# schematic.net
KiCad netlist of a schematic drawn in EasyEDA
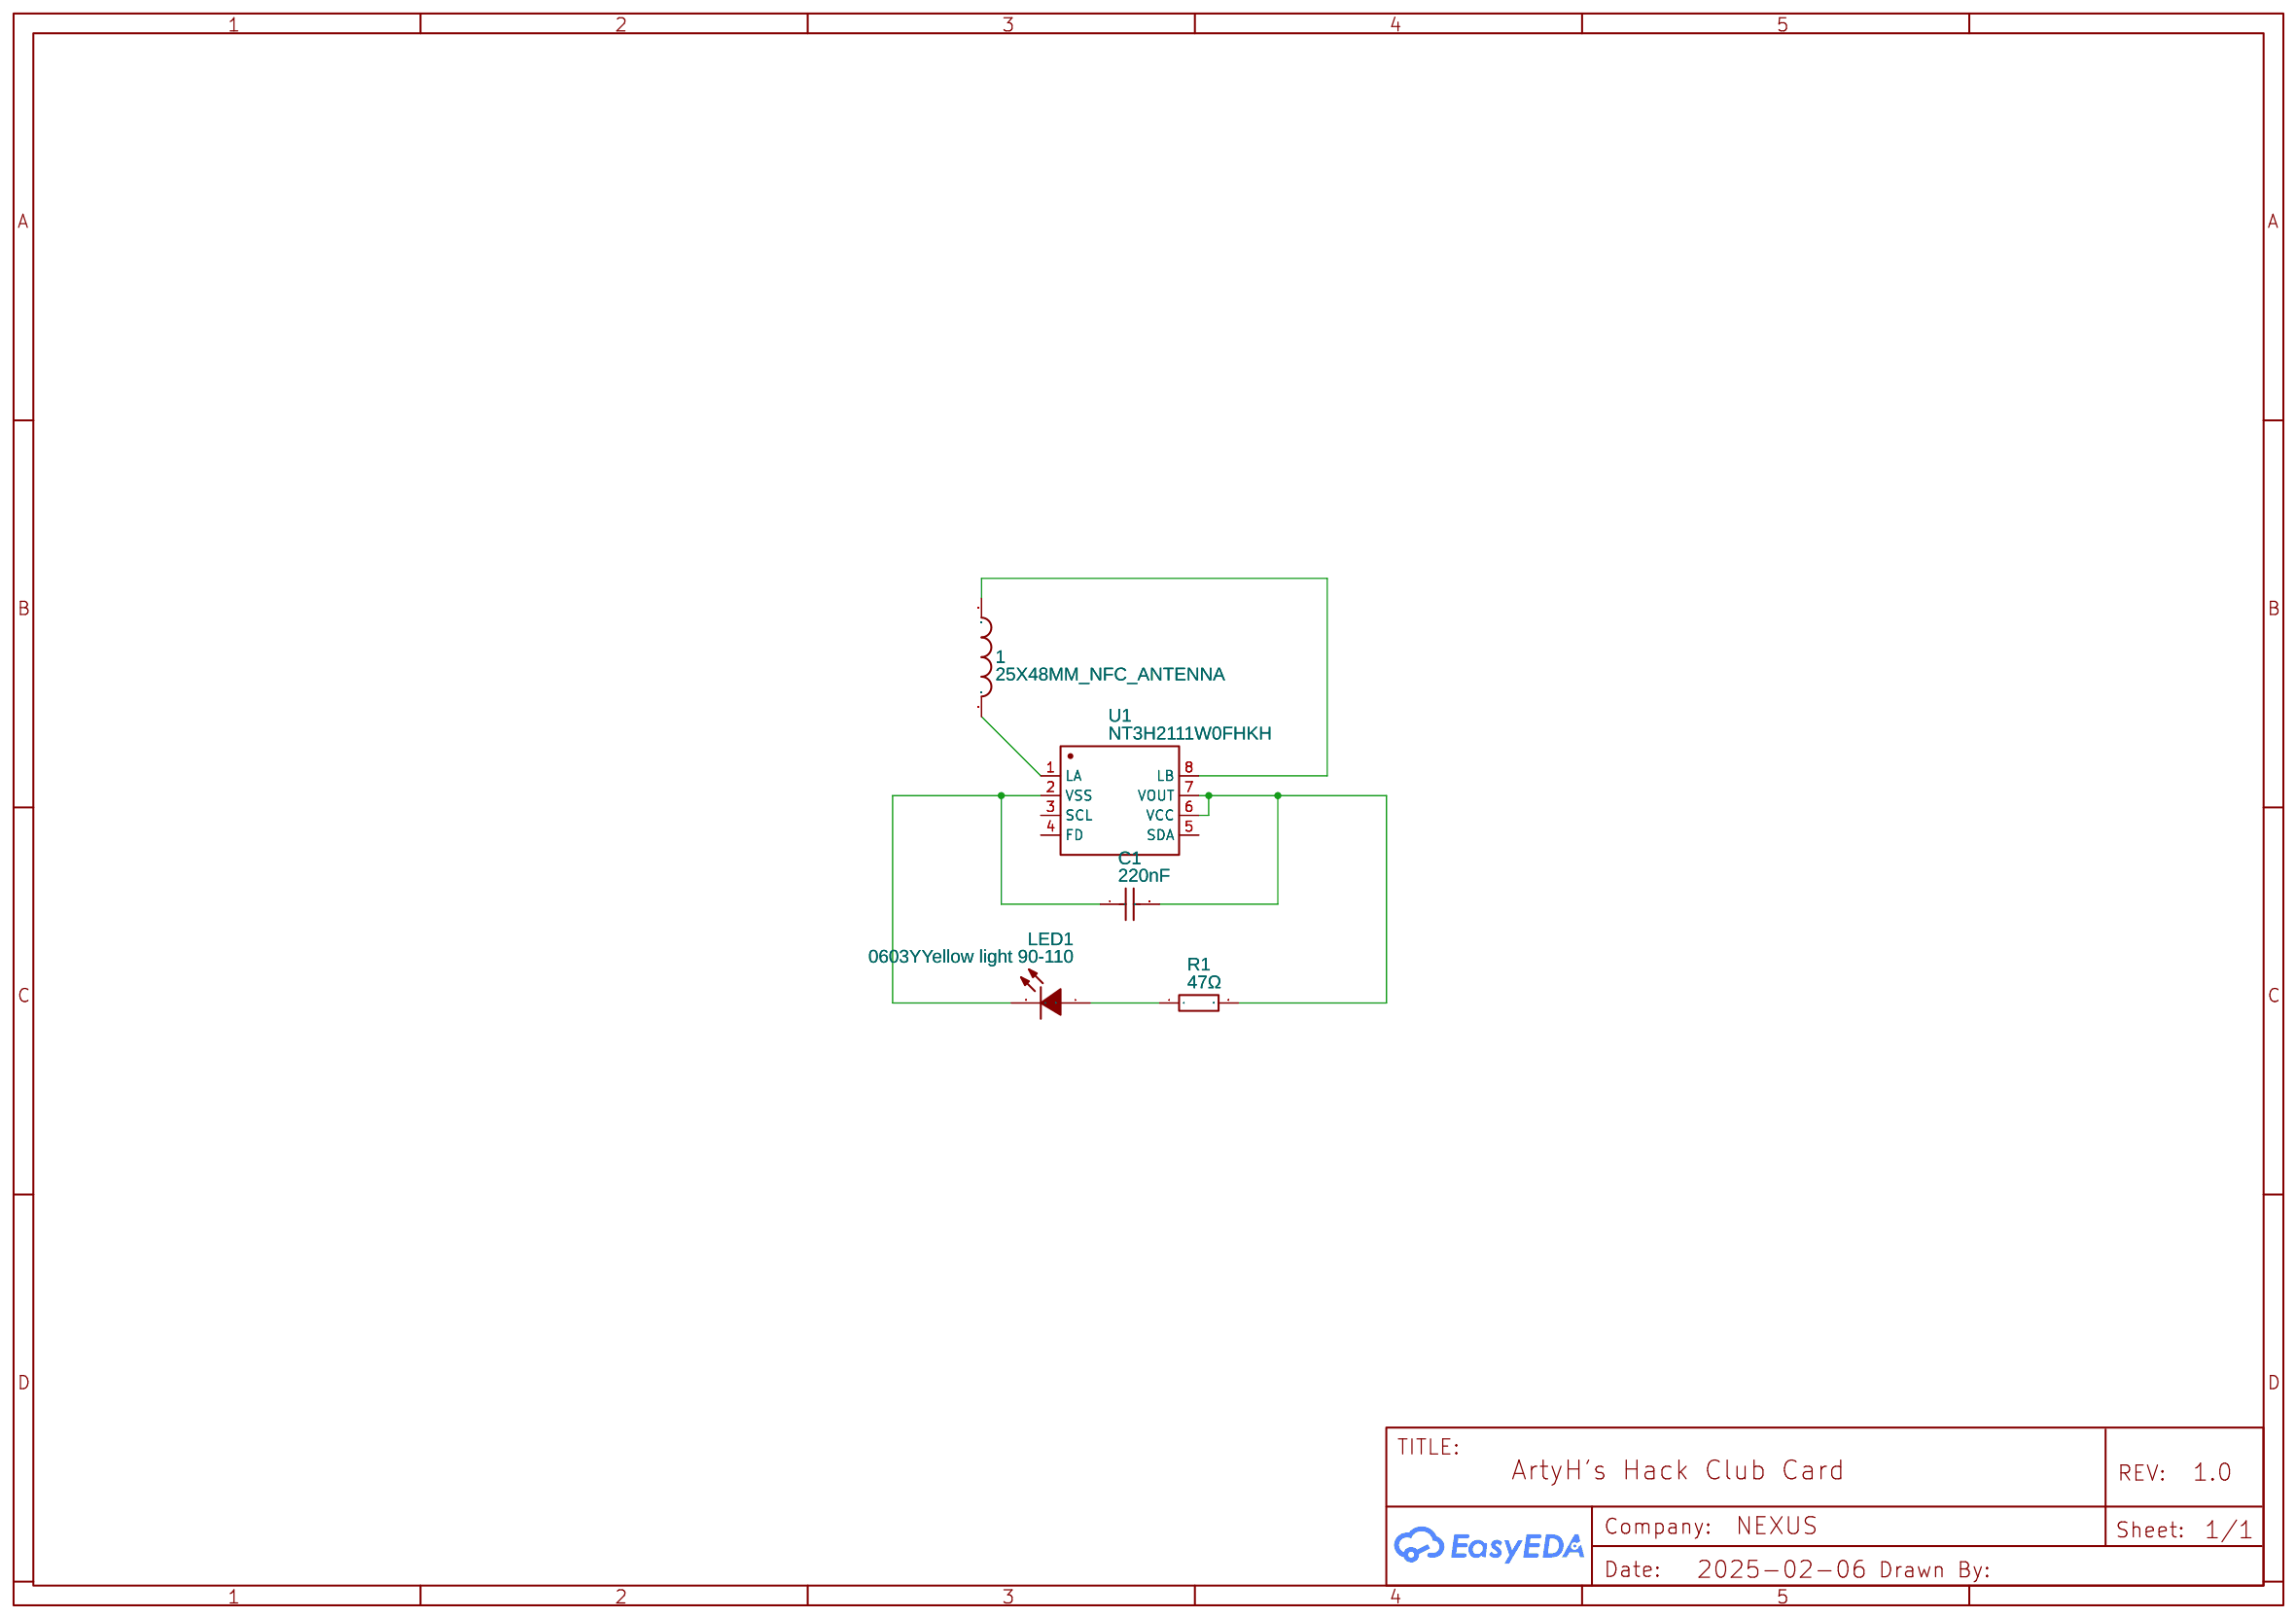
[diagram p0: schematic sheet]

(export (version "E")
  (design (tool "Eeschema 10.0.6"))
  (components
    (comp (ref "1") (value "25X48MM_NFC_ANTENNA") (libsource (lib "") (part "25X48MM_NFC_ANTENNA")))
    (comp (ref "C1")
      (value "220nF")
      (fields
        (field (name "Manufacturer Part") "CL10B224KA8NNNC")
        (field (name "Manufacturer") "SAMSUNG(三星)")
      )
      (libsource (lib "") (part "CL10B224KA8NNNC"))
    )
    (comp (ref "LED1")
      (value "0603YYellow light 90-110")
      (fields (field (name "Manufacturer Part") "KT-0603Y") (field (name "Manufacturer") "KENTO"))
      (libsource (lib "") (part "0603YYellow light 90-110"))
    )
    (comp (ref "R1")
      (value "47Ω")
      (fields
        (field (name "Manufacturer Part") "0603WAF470JT5E")
        (field (name "Manufacturer") "UNI-ROYAL(厚声)")
      )
      (libsource (lib "") (part "0603WAF470JT5E"))
    )
    (comp (ref "U1")
      (value "NT3H2111W0FHKH")
      (fields (field (name "Manufacturer") "NXP(恩智浦)"))
      (libsource (lib "") (part "NT3H2111W0FHKH"))
    )
  )
  (nets
    (net (code "1") (name "Net-(LED1-A)") (class "Default")
      (node (ref "LED1") (pin "1") (pinfunction "A_1") (pintype "unspecified"))
      (node (ref "R1") (pin "1") (pinfunction "1_1") (pintype "input"))
    )
    (net (code "2") (name "Net-(LED1-K)") (class "Default")
      (node (ref "C1") (pin "1") (pinfunction "1_1") (pintype "input"))
      (node (ref "LED1") (pin "2") (pinfunction "K_2") (pintype "unspecified"))
      (node (ref "U1") (pin "2") (pinfunction "VSS_2") (pintype "unspecified"))
    )
    (net (code "3") (name "Net-(U1-LA)") (class "Default")
      (node (ref "1") (pin "P$2") (pinfunction "P$2_P$2") (pintype "bidirectional"))
      (node (ref "U1") (pin "1") (pinfunction "LA_1") (pintype "unspecified"))
    )
    (net (code "4") (name "Net-(U1-LB)") (class "Default")
      (node (ref "1") (pin "P$1") (pinfunction "P$1_P$1") (pintype "bidirectional"))
      (node (ref "U1") (pin "8") (pinfunction "LB_8") (pintype "unspecified"))
    )
    (net (code "5") (name "Net-(U1-VCC)") (class "Default")
      (node (ref "C1") (pin "2") (pinfunction "2_2") (pintype "input"))
      (node (ref "R1") (pin "2") (pinfunction "2_2") (pintype "input"))
      (node (ref "U1") (pin "6") (pinfunction "VCC_6") (pintype "unspecified"))
      (node (ref "U1") (pin "7") (pinfunction "VOUT_7") (pintype "unspecified"))
    )
    (net (code "6") (name "unconnected-(U1-FD-Pad4)") (class "Default")
      (node (ref "U1") (pin "4") (pinfunction "FD_4") (pintype "unspecified"))
    )
    (net (code "7") (name "unconnected-(U1-SCL-Pad3)") (class "Default")
      (node (ref "U1") (pin "3") (pinfunction "SCL_3") (pintype "unspecified"))
    )
    (net (code "8") (name "unconnected-(U1-SDA-Pad5)") (class "Default")
      (node (ref "U1") (pin "5") (pinfunction "SDA_5") (pintype "unspecified"))
    )
  )
)
